# BATT_CPUPROG.net
KiCad netlist of a schematic drawn in EAGLE
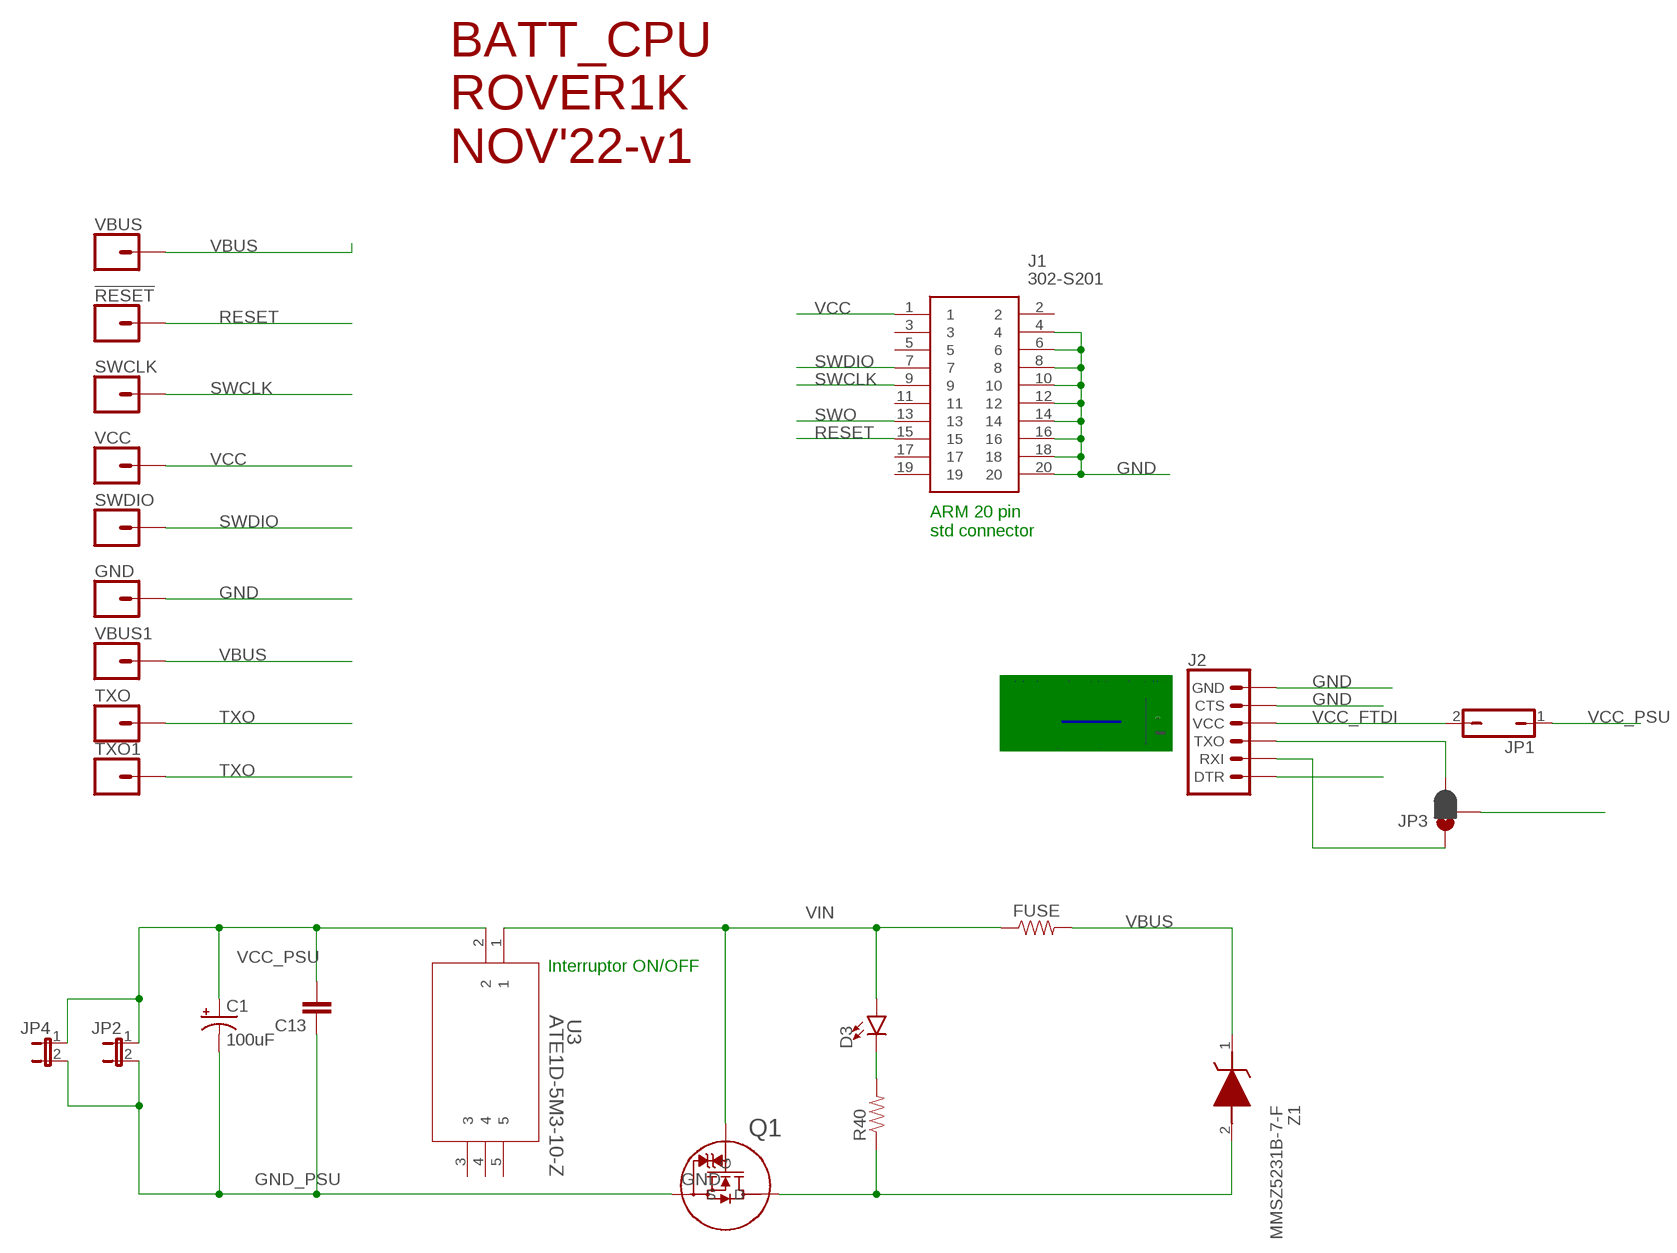
[diagram p0: schematic, sheet 1]

(export (version "E")
  (design (tool "Eeschema 10.0.6"))
  (components
    (comp (ref "!RESET")
      (value "CONN_01POGOPIN_HOLE_LARGE")
      (footprint "eagle-import:1X01_POGOPIN_HOLE_0.061_DIA")
      (libsource (lib "eagle-import") (part "CONN_01POGOPIN_HOLE_LARGE"))
    )
    (comp (ref "C1")
      (value "100uF")
      (footprint "eagle-import:CPOL-RADIAL-2.5MM-6.5MM")
      (libsource (lib "eagle-import") (part "100UF-POLAR-RADIAL-2.5MM-25V-20%"))
    )
    (comp (ref "C13")
      (value "C-EUC0805")
      (footprint "eagle-import:C0805")
      (libsource (lib "eagle-import") (part "C-EUC0805"))
    )
    (comp (ref "D3")
      (value "LED3MM")
      (footprint "eagle-import:LED_3MM")
      (libsource (lib "eagle-import") (part "LED3MM"))
    )
    (comp (ref "FUSE")
      (value "RESISTOR0805")
      (footprint "eagle-import:0805")
      (libsource (lib "eagle-import") (part "RESISTOR0805"))
    )
    (comp (ref "GND")
      (value "CONN_01POGOPIN_HOLE_LARGE")
      (footprint "eagle-import:1X01_POGOPIN_HOLE_0.061_DIA")
      (libsource (lib "eagle-import") (part "CONN_01POGOPIN_HOLE_LARGE"))
    )
    (comp (ref "J1")
      (value "302-S201")
      (footprint "eagle-import:SHDR20W66P254_2X10_3300X905X90")
      (libsource (lib "eagle-import") (part "302-S201"))
    )
    (comp (ref "J2")
      (value "6_PIN_SERIAL_TARGET")
      (footprint "eagle-import:1X06")
      (libsource (lib "eagle-import") (part "6_PIN_SERIAL_TARGET"))
    )
    (comp (ref "JP1")
      (value "JP1Q")
      (footprint "eagle-import:JP1")
      (libsource (lib "eagle-import") (part "JP1Q"))
    )
    (comp (ref "JP2")
      (value "JP1E")
      (footprint "eagle-import:JP1")
      (libsource (lib "eagle-import") (part "JP1E"))
    )
    (comp (ref "JP3")
      (value "JUMPER-SMT_3_1-NC_PASTE_NO-SILK")
      (footprint "eagle-import:SMT-JUMPER_3_1-NC_PASTE_NO-SILK")
      (libsource (lib "eagle-import") (part "JUMPER-SMT_3_1-NC_PASTE_NO-SILK"))
    )
    (comp (ref "JP4")
      (value "JP1E")
      (footprint "eagle-import:JP1")
      (libsource (lib "eagle-import") (part "JP1E"))
    )
    (comp (ref "Q1")
      (value "PJA3416AE_R1_00001")
      (footprint "eagle-import:SOT23_PJA3416_PNJ")
      (fields (field (name "COPYRIGHT") "Copyright (C) 2022 Ultra Librarian. All rights reserved."))
      (libsource (lib "eagle-import") (part "PJA3416AE_R1_00001"))
    )
    (comp (ref "R40")
      (value "10K")
      (footprint "eagle-import:0805")
      (libsource (lib "eagle-import") (part "RESISTOR0805-RES"))
    )
    (comp (ref "SWCLK")
      (value "CONN_01POGOPIN_HOLE_LARGE")
      (footprint "eagle-import:1X01_POGOPIN_HOLE_0.061_DIA")
      (libsource (lib "eagle-import") (part "CONN_01POGOPIN_HOLE_LARGE"))
    )
    (comp (ref "SWDIO")
      (value "CONN_01POGOPIN_HOLE_LARGE")
      (footprint "eagle-import:1X01_POGOPIN_HOLE_0.061_DIA")
      (libsource (lib "eagle-import") (part "CONN_01POGOPIN_HOLE_LARGE"))
    )
    (comp (ref "TXO")
      (value "CONN_01POGOPIN_HOLE_LARGE")
      (footprint "eagle-import:1X01_POGOPIN_HOLE_0.061_DIA")
      (libsource (lib "eagle-import") (part "CONN_01POGOPIN_HOLE_LARGE"))
    )
    (comp (ref "TXO1")
      (value "CONN_01POGOPIN_HOLE_LARGE")
      (footprint "eagle-import:1X01_POGOPIN_HOLE_0.061_DIA")
      (libsource (lib "eagle-import") (part "CONN_01POGOPIN_HOLE_LARGE"))
    )
    (comp (ref "U3")
      (value "ATE1D-5M3-10-Z")
      (footprint "eagle-import:SPDT05_ATE1D_9P5X8_NDC")
      (fields (field (name "COPYRIGHT") "Copyright (C) 2022 Ultra Librarian. All rights reserved."))
      (libsource (lib "eagle-import") (part "ATE1D-5M3-10-Z"))
    )
    (comp (ref "VBUS")
      (value "CONN_01POGOPIN_HOLE_LARGE")
      (footprint "eagle-import:1X01_POGOPIN_HOLE_0.061_DIA")
      (libsource (lib "eagle-import") (part "CONN_01POGOPIN_HOLE_LARGE"))
    )
    (comp (ref "VBUS1")
      (value "CONN_01POGOPIN_HOLE_LARGE")
      (footprint "eagle-import:1X01_POGOPIN_HOLE_0.061_DIA")
      (libsource (lib "eagle-import") (part "CONN_01POGOPIN_HOLE_LARGE"))
    )
    (comp (ref "VCC")
      (value "CONN_01POGOPIN_HOLE_LARGE")
      (footprint "eagle-import:1X01_POGOPIN_HOLE_0.061_DIA")
      (libsource (lib "eagle-import") (part "CONN_01POGOPIN_HOLE_LARGE"))
    )
    (comp (ref "Z1")
      (value "MMSZ5231B-7-F")
      (footprint "eagle-import:SOD3716X145N")
      (fields (field (name "MOUSER_PART_NUMBER") "621-MMSZ5231B-F"))
      (libsource (lib "eagle-import") (part "MMSZ5231B-7-F"))
    )
  )
  (nets
    (net (code "1") (name "/GND") (class "Default")
      (node (ref "GND") (pin "2") (pinfunction "1_2") (pintype "passive"))
      (node (ref "J1") (pin "10") (pinfunction "10_10") (pintype "bidirectional"))
      (node (ref "J1") (pin "12") (pinfunction "12_12") (pintype "bidirectional"))
      (node (ref "J1") (pin "14") (pinfunction "14_14") (pintype "bidirectional"))
      (node (ref "J1") (pin "16") (pinfunction "16_16") (pintype "bidirectional"))
      (node (ref "J1") (pin "18") (pinfunction "18_18") (pintype "bidirectional"))
      (node (ref "J1") (pin "20") (pinfunction "20_20") (pintype "bidirectional"))
      (node (ref "J1") (pin "4") (pinfunction "4_4") (pintype "bidirectional"))
      (node (ref "J1") (pin "6") (pinfunction "6_6") (pintype "bidirectional"))
      (node (ref "J1") (pin "8") (pinfunction "8_8") (pintype "bidirectional"))
      (node (ref "J2") (pin "5") (pinfunction "CTS_5") (pintype "passive"))
      (node (ref "J2") (pin "6") (pinfunction "GND_6") (pintype "passive"))
      (node (ref "Q1") (pin "3") (pinfunction "D_3") (pintype "passive"))
      (node (ref "R40") (pin "1") (pinfunction "1_1") (pintype "passive"))
      (node (ref "Z1") (pin "2") (pinfunction "A_2") (pintype "bidirectional"))
    )
    (net (code "2") (name "/GND_PSU") (class "Default")
      (node (ref "C1") (pin "2") (pinfunction "-_2") (pintype "passive"))
      (node (ref "C13") (pin "1") (pinfunction "1_1") (pintype "passive"))
      (node (ref "JP2") (pin "2") (pinfunction "2_2") (pintype "passive"))
      (node (ref "JP4") (pin "2") (pinfunction "2_2") (pintype "passive"))
      (node (ref "Q1") (pin "2") (pinfunction "S_2") (pintype "passive"))
    )
    (net (code "3") (name "/RESET") (class "Default")
      (node (ref "!RESET") (pin "2") (pinfunction "1_2") (pintype "passive"))
      (node (ref "J1") (pin "15") (pinfunction "15_15") (pintype "bidirectional"))
    )
    (net (code "4") (name "/SWCLK") (class "Default")
      (node (ref "J1") (pin "9") (pinfunction "9_9") (pintype "bidirectional"))
      (node (ref "SWCLK") (pin "2") (pinfunction "1_2") (pintype "passive"))
    )
    (net (code "5") (name "/SWDIO") (class "Default")
      (node (ref "J1") (pin "7") (pinfunction "7_7") (pintype "bidirectional"))
      (node (ref "SWDIO") (pin "2") (pinfunction "1_2") (pintype "passive"))
    )
    (net (code "6") (name "/SWO") (class "Default")
      (node (ref "J1") (pin "13") (pinfunction "13_13") (pintype "bidirectional"))
    )
    (net (code "7") (name "/TXO") (class "Default")
      (node (ref "JP3") (pin "2") (pinfunction "2_2") (pintype "passive"))
      (node (ref "TXO") (pin "2") (pinfunction "1_2") (pintype "passive"))
      (node (ref "TXO1") (pin "2") (pinfunction "1_2") (pintype "passive"))
    )
    (net (code "8") (name "/VBUS") (class "Default")
      (node (ref "FUSE") (pin "2") (pinfunction "2_2") (pintype "passive"))
      (node (ref "VBUS") (pin "2") (pinfunction "1_2") (pintype "passive"))
      (node (ref "VBUS1") (pin "2") (pinfunction "1_2") (pintype "passive"))
      (node (ref "Z1") (pin "1") (pinfunction "K_1") (pintype "bidirectional"))
    )
    (net (code "9") (name "/VCC") (class "Default")
      (node (ref "J1") (pin "1") (pinfunction "1_1") (pintype "bidirectional"))
      (node (ref "VCC") (pin "2") (pinfunction "1_2") (pintype "passive"))
    )
    (net (code "10") (name "/VCC_FTDI") (class "Default")
      (node (ref "J2") (pin "4") (pinfunction "VCC_4") (pintype "passive"))
      (node (ref "JP1") (pin "2") (pinfunction "2_2") (pintype "passive"))
    )
    (net (code "11") (name "/VCC_PSU") (class "Default")
      (node (ref "C1") (pin "1") (pinfunction "+_1") (pintype "passive"))
      (node (ref "C13") (pin "2") (pinfunction "2_2") (pintype "passive"))
      (node (ref "JP1") (pin "1") (pinfunction "1_1") (pintype "passive"))
      (node (ref "JP2") (pin "1") (pinfunction "1_1") (pintype "passive"))
      (node (ref "JP4") (pin "1") (pinfunction "1_1") (pintype "passive"))
      (node (ref "U3") (pin "2") (pinfunction "2_2") (pintype "passive"))
    )
    (net (code "12") (name "/VIN") (class "Default")
      (node (ref "D3") (pin "A") (pinfunction "A_A") (pintype "passive"))
      (node (ref "FUSE") (pin "1") (pinfunction "1_1") (pintype "passive"))
      (node (ref "Q1") (pin "1") (pinfunction "G_1") (pintype "passive"))
      (node (ref "U3") (pin "1") (pinfunction "1_1") (pintype "passive"))
    )
    (net (code "13") (name "Net-(D3-C)") (class "Default")
      (node (ref "D3") (pin "K") (pinfunction "C_K") (pintype "passive"))
      (node (ref "R40") (pin "2") (pinfunction "2_2") (pintype "passive"))
    )
    (net (code "14") (name "Net-(J2-RXI)") (class "Default")
      (node (ref "J2") (pin "2") (pinfunction "RXI_2") (pintype "passive"))
      (node (ref "JP3") (pin "1") (pinfunction "1_1") (pintype "passive"))
    )
    (net (code "15") (name "Net-(J2-TXO)") (class "Default")
      (node (ref "J2") (pin "3") (pinfunction "TXO_3") (pintype "passive"))
      (node (ref "JP3") (pin "3") (pinfunction "3_3") (pintype "passive"))
    )
    (net (code "16") (name "unconnected-(J1-Pad2)") (class "Default")
      (node (ref "J1") (pin "2") (pinfunction "2_2") (pintype "bidirectional"))
    )
    (net (code "17") (name "unconnected-(J1-Pad3)") (class "Default")
      (node (ref "J1") (pin "3") (pinfunction "3_3") (pintype "bidirectional"))
    )
    (net (code "18") (name "unconnected-(J1-Pad5)") (class "Default")
      (node (ref "J1") (pin "5") (pinfunction "5_5") (pintype "bidirectional"))
    )
    (net (code "19") (name "unconnected-(J1-Pad11)") (class "Default")
      (node (ref "J1") (pin "11") (pinfunction "11_11") (pintype "bidirectional"))
    )
    (net (code "20") (name "unconnected-(J1-Pad17)") (class "Default")
      (node (ref "J1") (pin "17") (pinfunction "17_17") (pintype "bidirectional"))
    )
    (net (code "21") (name "unconnected-(J1-Pad19)") (class "Default")
      (node (ref "J1") (pin "19") (pinfunction "19_19") (pintype "bidirectional"))
    )
    (net (code "22") (name "unconnected-(J2-DTR-Pad1)") (class "Default")
      (node (ref "J2") (pin "1") (pinfunction "DTR_1") (pintype "passive"))
    )
    (net (code "23") (name "unconnected-(U3-Pad3)") (class "Default")
      (node (ref "U3") (pin "3") (pinfunction "3_3") (pintype "passive"))
    )
    (net (code "24") (name "unconnected-(U3-Pad4)") (class "Default")
      (node (ref "U3") (pin "4") (pinfunction "4_4") (pintype "passive"))
    )
    (net (code "25") (name "unconnected-(U3-Pad5)") (class "Default")
      (node (ref "U3") (pin "5") (pinfunction "5_5") (pintype "passive"))
    )
  )
)
